# GeneratedSystem-02.net
KiCad netlist of a schematic drawn in Altium Designer
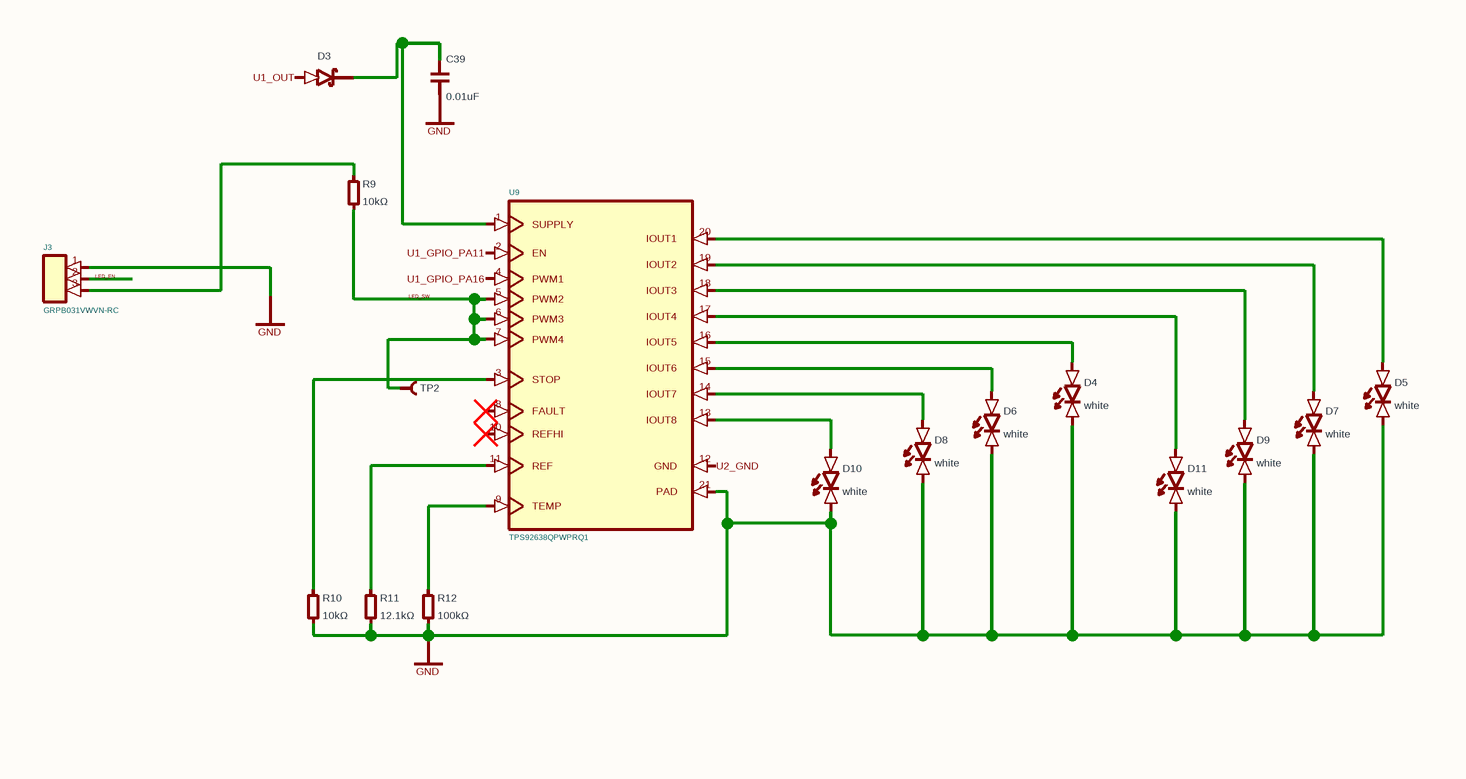
[diagram p0: GeneratedSystem-02.SchDoc]

(export (version "E")
  (design (tool "Eeschema 10.0.6"))
  (components
    (comp (ref "C39") (value "0.01uF") (libsource (lib "altium-import") (part "root_0_capacitor_down_")))
    (comp (ref "D3") (value "~") (libsource (lib "altium-import") (part "root_0_schottky_diode_right_")))
    (comp (ref "D4") (value "white") (libsource (lib "altium-import") (part "root_0_led_down_")))
    (comp (ref "D5") (value "white") (libsource (lib "altium-import") (part "root_0_led_down_")))
    (comp (ref "D6") (value "white") (libsource (lib "altium-import") (part "root_0_led_down_")))
    (comp (ref "D7") (value "white") (libsource (lib "altium-import") (part "root_0_led_down_")))
    (comp (ref "D8") (value "white") (libsource (lib "altium-import") (part "root_0_led_down_")))
    (comp (ref "D9") (value "white") (libsource (lib "altium-import") (part "root_0_led_down_")))
    (comp (ref "D10") (value "white") (libsource (lib "altium-import") (part "root_0_led_down_")))
    (comp (ref "D11") (value "white") (libsource (lib "altium-import") (part "root_0_led_down_")))
    (comp (ref "J3") (value "~") (libsource (lib "altium-import") (part "root_0_J3_")))
    (comp (ref "R9") (value "10kΩ") (libsource (lib "altium-import") (part "root_0_boxresistor_down_")))
    (comp (ref "R10") (value "10kΩ") (libsource (lib "altium-import") (part "root_0_boxresistor_down_")))
    (comp (ref "R11") (value "12.1kΩ") (libsource (lib "altium-import") (part "root_0_boxresistor_down_")))
    (comp (ref "R12") (value "100kΩ") (libsource (lib "altium-import") (part "root_0_boxresistor_down_")))
    (comp (ref "TP2") (value "~") (libsource (lib "altium-import") (part "root_0_testpoint_right_")))
    (comp (ref "U9") (value "~") (libsource (lib "altium-import") (part "root_0_U9_")))
  )
  (nets
    (net (code "1") (name "/U1_GPIO_PA11") (class "Default")
      (node (ref "U9") (pin "2") (pinfunction "EN_2") (pintype "input"))
    )
    (net (code "2") (name "/U1_GPIO_PA16") (class "Default")
      (node (ref "U9") (pin "4") (pinfunction "PWM1_4") (pintype "input"))
    )
    (net (code "3") (name "/U1_OUT") (class "Default")
      (node (ref "D3") (pin "1") (pinfunction "pos_1") (pintype "input"))
    )
    (net (code "4") (name "/U2_GND") (class "Default")
      (node (ref "U9") (pin "12") (pinfunction "GND_12") (pintype "input"))
    )
    (net (code "5") (name "GND") (class "Default")
      (node (ref "C39") (pin "2") (pinfunction "cathode_2") (pintype "input"))
      (node (ref "D10") (pin "2") (pinfunction "cathode_2") (pintype "input"))
      (node (ref "D11") (pin "2") (pinfunction "cathode_2") (pintype "input"))
      (node (ref "D4") (pin "2") (pinfunction "cathode_2") (pintype "input"))
      (node (ref "D5") (pin "2") (pinfunction "cathode_2") (pintype "input"))
      (node (ref "D6") (pin "2") (pinfunction "cathode_2") (pintype "input"))
      (node (ref "D7") (pin "2") (pinfunction "cathode_2") (pintype "input"))
      (node (ref "D8") (pin "2") (pinfunction "cathode_2") (pintype "input"))
      (node (ref "D9") (pin "2") (pinfunction "cathode_2") (pintype "input"))
      (node (ref "J3") (pin "1") (pinfunction "pin1_1") (pintype "input"))
      (node (ref "R10") (pin "2") (pinfunction "cathode_2") (pintype "input"))
      (node (ref "R11") (pin "2") (pinfunction "cathode_2") (pintype "input"))
      (node (ref "R12") (pin "2") (pinfunction "cathode_2") (pintype "input"))
      (node (ref "U9") (pin "21") (pinfunction "PAD_21") (pintype "input"))
    )
    (net (code "6") (name "Net-(C39-anode)") (class "Default")
      (node (ref "C39") (pin "1") (pinfunction "anode_1") (pintype "input"))
      (node (ref "D3") (pin "2") (pinfunction "neg_2") (pintype "input"))
      (node (ref "U9") (pin "1") (pinfunction "SUPPLY_1") (pintype "input"))
    )
    (net (code "7") (name "Net-(D4-anode)") (class "Default")
      (node (ref "D4") (pin "1") (pinfunction "anode_1") (pintype "input"))
      (node (ref "U9") (pin "16") (pinfunction "IOUT5_16") (pintype "input"))
    )
    (net (code "8") (name "Net-(D5-anode)") (class "Default")
      (node (ref "D5") (pin "1") (pinfunction "anode_1") (pintype "input"))
      (node (ref "U9") (pin "20") (pinfunction "IOUT1_20") (pintype "input"))
    )
    (net (code "9") (name "Net-(D6-anode)") (class "Default")
      (node (ref "D6") (pin "1") (pinfunction "anode_1") (pintype "input"))
      (node (ref "U9") (pin "15") (pinfunction "IOUT6_15") (pintype "input"))
    )
    (net (code "10") (name "Net-(D7-anode)") (class "Default")
      (node (ref "D7") (pin "1") (pinfunction "anode_1") (pintype "input"))
      (node (ref "U9") (pin "19") (pinfunction "IOUT2_19") (pintype "input"))
    )
    (net (code "11") (name "Net-(D8-anode)") (class "Default")
      (node (ref "D8") (pin "1") (pinfunction "anode_1") (pintype "input"))
      (node (ref "U9") (pin "14") (pinfunction "IOUT7_14") (pintype "input"))
    )
    (net (code "12") (name "Net-(D9-anode)") (class "Default")
      (node (ref "D9") (pin "1") (pinfunction "anode_1") (pintype "input"))
      (node (ref "U9") (pin "18") (pinfunction "IOUT3_18") (pintype "input"))
    )
    (net (code "13") (name "Net-(D10-anode)") (class "Default")
      (node (ref "D10") (pin "1") (pinfunction "anode_1") (pintype "input"))
      (node (ref "U9") (pin "13") (pinfunction "IOUT8_13") (pintype "input"))
    )
    (net (code "14") (name "Net-(D11-anode)") (class "Default")
      (node (ref "D11") (pin "1") (pinfunction "anode_1") (pintype "input"))
      (node (ref "U9") (pin "17") (pinfunction "IOUT4_17") (pintype "input"))
    )
    (net (code "15") (name "Net-(J3-pin3)") (class "Default")
      (node (ref "J3") (pin "3") (pinfunction "pin3_3") (pintype "input"))
      (node (ref "R9") (pin "1") (pinfunction "anode_1") (pintype "input"))
    )
    (net (code "16") (name "Net-(R9-cathode)") (class "Default")
      (node (ref "R9") (pin "2") (pinfunction "cathode_2") (pintype "input"))
      (node (ref "TP2") (pin "1") (pinfunction "pin1_1") (pintype "input"))
      (node (ref "U9") (pin "5") (pinfunction "PWM2_5") (pintype "input"))
      (node (ref "U9") (pin "6") (pinfunction "PWM3_6") (pintype "input"))
      (node (ref "U9") (pin "7") (pinfunction "PWM4_7") (pintype "input"))
    )
    (net (code "17") (name "Net-(R10-anode)") (class "Default")
      (node (ref "R10") (pin "1") (pinfunction "anode_1") (pintype "input"))
      (node (ref "U9") (pin "3") (pinfunction "STOP_3") (pintype "input"))
    )
    (net (code "18") (name "Net-(R11-anode)") (class "Default")
      (node (ref "R11") (pin "1") (pinfunction "anode_1") (pintype "input"))
      (node (ref "U9") (pin "11") (pinfunction "REF_11") (pintype "input"))
    )
    (net (code "19") (name "Net-(R12-anode)") (class "Default")
      (node (ref "R12") (pin "1") (pinfunction "anode_1") (pintype "input"))
      (node (ref "U9") (pin "9") (pinfunction "TEMP_9") (pintype "input"))
    )
    (net (code "20") (name "unconnected-(J3-pin2-Pad2)") (class "Default")
      (node (ref "J3") (pin "2") (pinfunction "pin2_2") (pintype "input"))
    )
    (net (code "21") (name "unconnected-(U9-FAULT-Pad8)") (class "Default")
      (node (ref "U9") (pin "8") (pinfunction "FAULT_8") (pintype "input+no_connect"))
    )
    (net (code "22") (name "unconnected-(U9-REFHI-Pad10)") (class "Default")
      (node (ref "U9") (pin "10") (pinfunction "REFHI_10") (pintype "input+no_connect"))
    )
  )
)
